# reciever_circuit.net
KiCad netlist of a schematic drawn in EAGLE
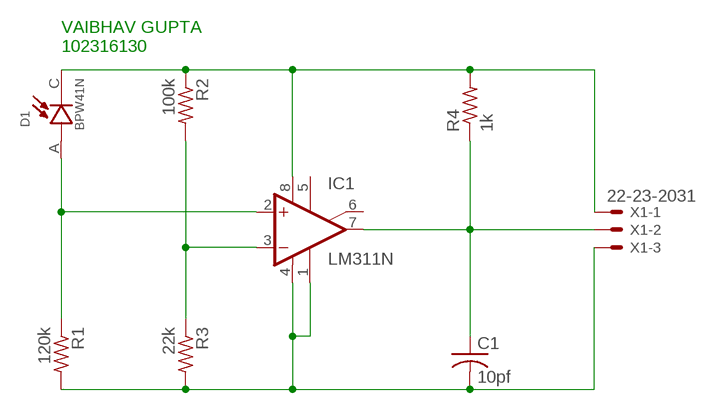
[diagram p0: schematic, sheet 1]

(export (version "E")
  (design (tool "Eeschema 10.0.6"))
  (components
    (comp (ref "C1")
      (value "10pf")
      (footprint "eagle-import:C025-024X044")
      (libsource (lib "eagle-import") (part "C-US025-024X044"))
    )
    (comp (ref "D1")
      (value "BPW41N")
      (footprint "eagle-import:DIO_BPW41N")
      (fields (field (name "MF") "Vishay Semiconductor Opto Division"))
      (libsource (lib "eagle-import") (part "BPW41N"))
    )
    (comp (ref "IC1")
      (value "LM311N")
      (footprint "eagle-import:DIL08")
      (libsource (lib "eagle-import") (part "LM311N"))
    )
    (comp (ref "R1")
      (value "120k")
      (footprint "eagle-import:0204_5")
      (libsource (lib "eagle-import") (part "R-US_0204/5"))
    )
    (comp (ref "R2")
      (value "100k")
      (footprint "eagle-import:0204_5")
      (libsource (lib "eagle-import") (part "R-US_0204/5"))
    )
    (comp (ref "R3")
      (value "22k")
      (footprint "eagle-import:0204_5")
      (libsource (lib "eagle-import") (part "R-US_0204/5"))
    )
    (comp (ref "R4")
      (value "1k")
      (footprint "eagle-import:0204_5")
      (libsource (lib "eagle-import") (part "R-US_0204/5"))
    )
    (comp (ref "X1")
      (value "22-23-2031")
      (footprint "eagle-import:22-23-2031")
      (fields (field (name "MF") "MOLEX"))
      (libsource (lib "eagle-import") (part "22-23-2031"))
    )
  )
  (nets
    (net (code "1") (name "Net-(IC1-+IN)") (class "Default")
      (node (ref "D1") (pin "A") (pinfunction "A_A") (pintype "passive"))
      (node (ref "IC1") (pin "2") (pinfunction "+IN_2") (pintype "input"))
      (node (ref "R1") (pin "1") (pinfunction "1_1") (pintype "passive"))
    )
    (net (code "2") (name "Net-(IC1--IN)") (class "Default")
      (node (ref "IC1") (pin "3") (pinfunction "-IN_3") (pintype "input"))
      (node (ref "R2") (pin "2") (pinfunction "2_2") (pintype "passive"))
      (node (ref "R3") (pin "1") (pinfunction "1_1") (pintype "passive"))
    )
    (net (code "3") (name "Net-(IC1-GND)") (class "Default")
      (node (ref "C1") (pin "2") (pinfunction "2_2") (pintype "passive"))
      (node (ref "IC1") (pin "1") (pinfunction "GND_1") (pintype "passive"))
      (node (ref "IC1") (pin "4") (pinfunction "V-_4") (pintype "power_in"))
      (node (ref "R1") (pin "2") (pinfunction "2_2") (pintype "passive"))
      (node (ref "R3") (pin "2") (pinfunction "2_2") (pintype "passive"))
      (node (ref "X1") (pin "3") (pinfunction "S_3") (pintype "passive"))
    )
    (net (code "4") (name "Net-(IC1-OUT)") (class "Default")
      (node (ref "C1") (pin "1") (pinfunction "1_1") (pintype "passive"))
      (node (ref "IC1") (pin "7") (pinfunction "OUT_7") (pintype "output"))
      (node (ref "R4") (pin "1") (pinfunction "1_1") (pintype "passive"))
      (node (ref "X1") (pin "2") (pinfunction "S_2") (pintype "passive"))
    )
    (net (code "5") (name "Net-(IC1-V+)") (class "Default")
      (node (ref "D1") (pin "C") (pinfunction "C_C") (pintype "passive"))
      (node (ref "IC1") (pin "8") (pinfunction "V+_8") (pintype "power_in"))
      (node (ref "R2") (pin "1") (pinfunction "1_1") (pintype "passive"))
      (node (ref "R4") (pin "2") (pinfunction "2_2") (pintype "passive"))
      (node (ref "X1") (pin "1") (pinfunction "S_1") (pintype "passive"))
    )
    (net (code "6") (name "unconnected-(IC1-ON-Pad5)") (class "Default")
      (node (ref "IC1") (pin "5") (pinfunction "ON_5") (pintype "passive"))
    )
    (net (code "7") (name "unconnected-(IC1-ON{slash}STR-Pad6)") (class "Default")
      (node (ref "IC1") (pin "6") (pinfunction "ON/STR_6") (pintype "passive"))
    )
  )
)
